# v007_schematics.net
KiCad netlist of a schematic drawn in Altium Designer
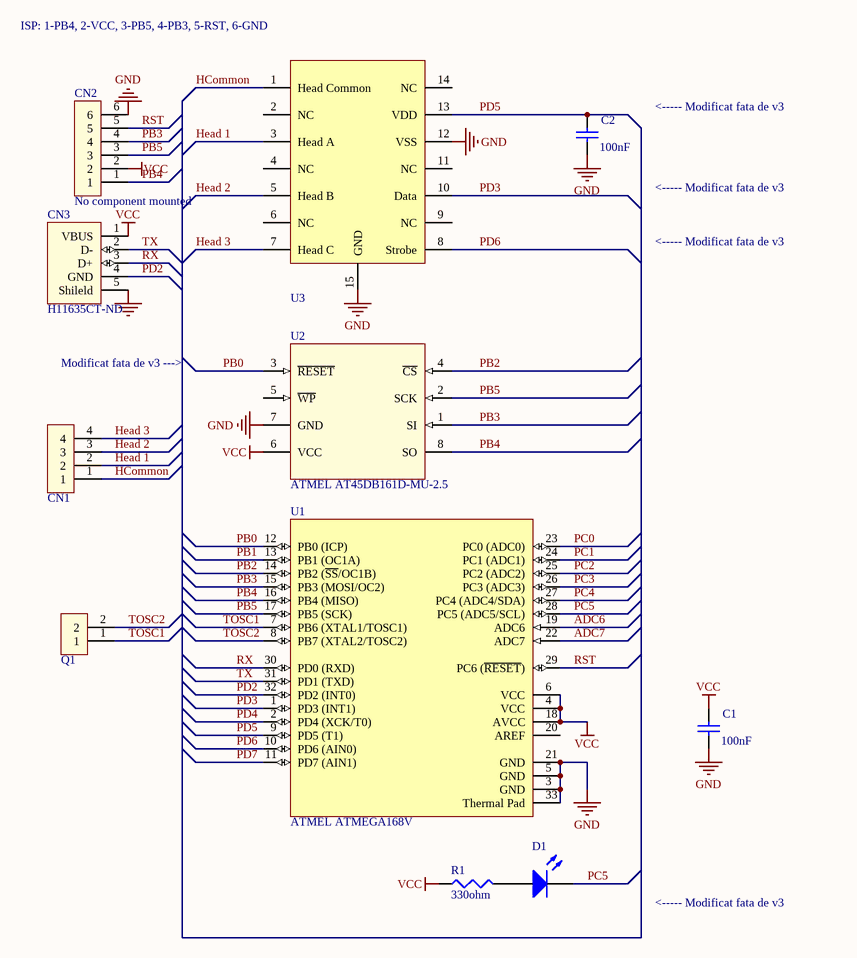
[diagram p0: v007 schematics.SCHDOC]

(export (version "E")
  (design (tool "Eeschema 10.0.6"))
  (components
    (comp (ref "C1")
      (value "100nF")
      (footprint "CC0603(0201)")
      (description "Capacitor 100nf")
      (fields (field (name "Comment") "490-3167-1-ND") (field (name "PUBLISHER") "Altium Limited"))
      (libsource (lib "Miscellaneous Devices") (part "Cap"))
    )
    (comp (ref "C2")
      (value "100nF")
      (footprint "CC0603(0201)")
      (description "Capacitor 100nF")
      (fields (field (name "Comment") "490-3167-1-ND") (field (name "PUBLISHER") "Altium Limited"))
      (libsource (lib "Miscellaneous Devices") (part "Cap"))
    )
    (comp (ref "CN1")
      (value "No component mounted")
      (footprint "SU04LS")
      (libsource (lib "v4lib") (part "4pin smd"))
    )
    (comp (ref "CN2")
      (value "No component mounted")
      (footprint "SU06LST")
      (libsource (lib "v4lib") (part "6pin smd"))
    )
    (comp (ref "CN3")
      (value "H11635CT-ND")
      (footprint "Micro USB Receptacle small")
      (description "CONN RCPT MICRO USB AB SMD R/A")
      (libsource (lib "v4lib") (part "micro usb"))
    )
    (comp (ref "D1")
      (value "511-1615-1-ND")
      (footprint "CC1005(0402)")
      (description "Typical BLUE SiC LED")
      (fields (field (name "PUBLISHER") "Altium Limited"))
      (libsource (lib "Miscellaneous Devices") (part "LED3"))
    )
    (comp (ref "Q1")
      (value "535-9542-1-ND")
      (footprint "Quartz SMD (small)")
      (description "32.768khz crystal 1.5 x 3.2mm")
      (libsource (lib "v4lib") (part "2pin smd"))
    )
    (comp (ref "R1")
      (value "330ohm")
      (footprint "CC0603(0201)")
      (description "Resistor 330ohm")
      (fields (field (name "Comment") "P330AGCT-ND") (field (name "PUBLISHER") "Altium Limited"))
      (libsource (lib "Miscellaneous Devices") (part "Res3"))
    )
    (comp (ref "U1")
      (value "ATMEL ATMEGA168V")
      (footprint "32M1-A L 3")
      (description "8-Bit AVR Microcontroller")
      (fields (field (name "PUBLISHER") "Altium Limited"))
      (libsource (lib "Atmel Microcontroller 8-Bit AVR") (part "ATmega8L-8MC"))
    )
    (comp (ref "U2")
      (value "ATMEL AT45DB161D-MU-2.5")
      (footprint "8m1-a mlf 2")
      (description "ATMEL 16MBit DataFlash")
      (libsource (lib "v4lib") (part "at45db041b"))
    )
    (comp (ref "U3")
      (value "Delta Asic")
      (footprint "delta asic - 4")
      (libsource (lib "v4lib") (part "delta asic 3volt"))
    )
  )
  (nets
    (net (code "1") (name "/ADC6") (class "Default")
      (node (ref "U1") (pin "19") (pinfunction "ADC6_19") (pintype "input"))
    )
    (net (code "2") (name "/ADC7") (class "Default")
      (node (ref "U1") (pin "22") (pinfunction "ADC7_22") (pintype "input"))
    )
    (net (code "3") (name "/HCommon") (class "Default")
      (node (ref "CN1") (pin "1") (pinfunction "1_1") (pintype "passive"))
      (node (ref "U3") (pin "1") (pinfunction "Head_Common_1") (pintype "passive"))
    )
    (net (code "4") (name "/Head 1") (class "Default")
      (node (ref "CN1") (pin "2") (pinfunction "2_2") (pintype "passive"))
      (node (ref "U3") (pin "3") (pinfunction "Head_A_3") (pintype "passive"))
    )
    (net (code "5") (name "/Head 2") (class "Default")
      (node (ref "CN1") (pin "3") (pinfunction "3_3") (pintype "passive"))
      (node (ref "U3") (pin "5") (pinfunction "Head_B_5") (pintype "passive"))
    )
    (net (code "6") (name "/Head 3") (class "Default")
      (node (ref "CN1") (pin "4") (pinfunction "4_4") (pintype "passive"))
      (node (ref "U3") (pin "7") (pinfunction "Head_C_7") (pintype "passive"))
    )
    (net (code "7") (name "/PB0") (class "Default")
      (node (ref "U1") (pin "12") (pinfunction "PB0_(ICP)_12") (pintype "bidirectional"))
      (node (ref "U2") (pin "3") (pinfunction "~{RESET}_3") (pintype "input"))
    )
    (net (code "8") (name "/PB1") (class "Default")
      (node (ref "U1") (pin "13") (pinfunction "PB1_(OC1A)_13") (pintype "bidirectional"))
    )
    (net (code "9") (name "/PB2") (class "Default")
      (node (ref "U1") (pin "14") (pinfunction "PB2_(~{SS}/OC1B)_14") (pintype "bidirectional"))
      (node (ref "U2") (pin "4") (pinfunction "~{CS}_4") (pintype "input"))
    )
    (net (code "10") (name "/PB3") (class "Default")
      (node (ref "CN2") (pin "4") (pinfunction "4_4") (pintype "passive"))
      (node (ref "U1") (pin "15") (pinfunction "PB3_(MOSI/OC2)_15") (pintype "bidirectional"))
      (node (ref "U2") (pin "1") (pinfunction "SI_1") (pintype "input"))
    )
    (net (code "11") (name "/PB4") (class "Default")
      (node (ref "CN2") (pin "1") (pinfunction "1_1") (pintype "passive"))
      (node (ref "U1") (pin "16") (pinfunction "PB4_(MISO)_16") (pintype "bidirectional"))
      (node (ref "U2") (pin "8") (pinfunction "SO_8") (pintype "passive"))
    )
    (net (code "12") (name "/PB5") (class "Default")
      (node (ref "CN2") (pin "3") (pinfunction "3_3") (pintype "passive"))
      (node (ref "U1") (pin "17") (pinfunction "PB5_(SCK)_17") (pintype "bidirectional"))
      (node (ref "U2") (pin "2") (pinfunction "SCK_2") (pintype "input"))
    )
    (net (code "13") (name "/PC0") (class "Default")
      (node (ref "U1") (pin "23") (pinfunction "PC0_(ADC0)_23") (pintype "bidirectional"))
    )
    (net (code "14") (name "/PC1") (class "Default")
      (node (ref "U1") (pin "24") (pinfunction "PC1_(ADC1)_24") (pintype "bidirectional"))
    )
    (net (code "15") (name "/PC2") (class "Default")
      (node (ref "U1") (pin "25") (pinfunction "PC2_(ADC2)_25") (pintype "bidirectional"))
    )
    (net (code "16") (name "/PC3") (class "Default")
      (node (ref "U1") (pin "26") (pinfunction "PC3_(ADC3)_26") (pintype "bidirectional"))
    )
    (net (code "17") (name "/PC4") (class "Default")
      (node (ref "U1") (pin "27") (pinfunction "PC4_(ADC4/SDA)_27") (pintype "bidirectional"))
    )
    (net (code "18") (name "/PC5") (class "Default")
      (node (ref "D1") (pin "2") (pinfunction "K_2") (pintype "passive"))
      (node (ref "U1") (pin "28") (pinfunction "PC5_(ADC5/SCL)_28") (pintype "bidirectional"))
    )
    (net (code "19") (name "/PD2") (class "Default")
      (node (ref "CN3") (pin "4") (pinfunction "GND_4") (pintype "passive"))
      (node (ref "U1") (pin "32") (pinfunction "PD2_(INT0)_32") (pintype "bidirectional"))
    )
    (net (code "20") (name "/PD3") (class "Default")
      (node (ref "U1") (pin "1") (pinfunction "PD3_(INT1)_1") (pintype "bidirectional"))
      (node (ref "U3") (pin "10") (pinfunction "Data_10") (pintype "passive"))
    )
    (net (code "21") (name "/PD4") (class "Default")
      (node (ref "U1") (pin "2") (pinfunction "PD4_(XCK/T0)_2") (pintype "bidirectional"))
    )
    (net (code "22") (name "/PD5") (class "Default")
      (node (ref "C2") (pin "1") (pinfunction "1_1") (pintype "passive"))
      (node (ref "U1") (pin "9") (pinfunction "PD5_(T1)_9") (pintype "bidirectional"))
      (node (ref "U3") (pin "13") (pinfunction "VDD_13") (pintype "passive"))
    )
    (net (code "23") (name "/PD6") (class "Default")
      (node (ref "U1") (pin "10") (pinfunction "PD6_(AIN0)_10") (pintype "bidirectional"))
      (node (ref "U3") (pin "8") (pinfunction "Strobe_8") (pintype "passive"))
    )
    (net (code "24") (name "/PD7") (class "Default")
      (node (ref "U1") (pin "11") (pinfunction "PD7_(AIN1)_11") (pintype "bidirectional"))
    )
    (net (code "25") (name "/RST") (class "Default")
      (node (ref "CN2") (pin "5") (pinfunction "5_5") (pintype "passive"))
      (node (ref "U1") (pin "29") (pinfunction "PC6_(~{RESET})_29") (pintype "bidirectional"))
    )
    (net (code "26") (name "/RX") (class "Default")
      (node (ref "CN3") (pin "3") (pinfunction "D+_3") (pintype "bidirectional"))
      (node (ref "U1") (pin "30") (pinfunction "PD0_(RXD)_30") (pintype "bidirectional"))
    )
    (net (code "27") (name "/TOSC1") (class "Default")
      (node (ref "Q1") (pin "1") (pinfunction "1_1") (pintype "passive"))
      (node (ref "U1") (pin "7") (pinfunction "PB6_(XTAL1/TOSC1)_7") (pintype "bidirectional"))
    )
    (net (code "28") (name "/TOSC2") (class "Default")
      (node (ref "Q1") (pin "2") (pinfunction "2_2") (pintype "passive"))
      (node (ref "U1") (pin "8") (pinfunction "PB7_(XTAL2/TOSC2)_8") (pintype "bidirectional"))
    )
    (net (code "29") (name "/TX") (class "Default")
      (node (ref "CN3") (pin "2") (pinfunction "D-_2") (pintype "bidirectional"))
      (node (ref "U1") (pin "31") (pinfunction "PD1_(TXD)_31") (pintype "bidirectional"))
    )
    (net (code "30") (name "GND") (class "Default")
      (node (ref "C1") (pin "2") (pinfunction "2_2") (pintype "passive"))
      (node (ref "C2") (pin "2") (pinfunction "2_2") (pintype "passive"))
      (node (ref "CN2") (pin "6") (pinfunction "6_6") (pintype "passive"))
      (node (ref "CN3") (pin "5") (pinfunction "Shileld_5") (pintype "passive"))
      (node (ref "U1") (pin "21") (pinfunction "GND_21") (pintype "power_in"))
      (node (ref "U1") (pin "3") (pinfunction "GND_3") (pintype "power_in"))
      (node (ref "U1") (pin "33") (pinfunction "Thermal_Pad_33") (pintype "power_in"))
      (node (ref "U1") (pin "5") (pinfunction "GND_5") (pintype "power_in"))
      (node (ref "U2") (pin "7") (pinfunction "GND_7") (pintype "passive"))
      (node (ref "U3") (pin "12") (pinfunction "VSS_12") (pintype "passive"))
      (node (ref "U3") (pin "15") (pinfunction "GND_15") (pintype "passive"))
    )
    (net (code "31") (name "Net-(D1-A)") (class "Default")
      (node (ref "D1") (pin "1") (pinfunction "A_1") (pintype "passive"))
      (node (ref "R1") (pin "2") (pinfunction "2_2") (pintype "passive"))
    )
    (net (code "32") (name "VCC") (class "Default")
      (node (ref "C1") (pin "1") (pinfunction "1_1") (pintype "passive"))
      (node (ref "CN2") (pin "2") (pinfunction "2_2") (pintype "passive"))
      (node (ref "CN3") (pin "1") (pinfunction "VBUS_1") (pintype "power_in"))
      (node (ref "R1") (pin "1") (pinfunction "1_1") (pintype "passive"))
      (node (ref "U1") (pin "18") (pinfunction "AVCC_18") (pintype "power_in"))
      (node (ref "U1") (pin "4") (pinfunction "VCC_4") (pintype "power_in"))
      (node (ref "U1") (pin "6") (pinfunction "VCC_6") (pintype "power_in"))
      (node (ref "U2") (pin "6") (pinfunction "VCC_6") (pintype "power_in"))
    )
    (net (code "33") (name "unconnected-(U1-AREF-Pad20)") (class "Default")
      (node (ref "U1") (pin "20") (pinfunction "AREF_20") (pintype "passive"))
    )
    (net (code "34") (name "unconnected-(U2-~{WP}-Pad5)") (class "Default")
      (node (ref "U2") (pin "5") (pinfunction "~{WP}_5") (pintype "input"))
    )
    (net (code "35") (name "unconnected-(U3-NC-Pad2)") (class "Default")
      (node (ref "U3") (pin "2") (pinfunction "NC_2") (pintype "passive"))
    )
    (net (code "36") (name "unconnected-(U3-NC-Pad4)") (class "Default")
      (node (ref "U3") (pin "4") (pinfunction "NC_4") (pintype "passive"))
    )
    (net (code "37") (name "unconnected-(U3-NC-Pad6)") (class "Default")
      (node (ref "U3") (pin "6") (pinfunction "NC_6") (pintype "passive"))
    )
    (net (code "38") (name "unconnected-(U3-NC-Pad9)") (class "Default")
      (node (ref "U3") (pin "9") (pinfunction "NC_9") (pintype "passive"))
    )
    (net (code "39") (name "unconnected-(U3-NC-Pad11)") (class "Default")
      (node (ref "U3") (pin "11") (pinfunction "NC_11") (pintype "passive"))
    )
    (net (code "40") (name "unconnected-(U3-NC-Pad14)") (class "Default")
      (node (ref "U3") (pin "14") (pinfunction "NC_14") (pintype "passive"))
    )
  )
)
